# Decoupling_Board.net
KiCad netlist of a schematic drawn in EAGLE
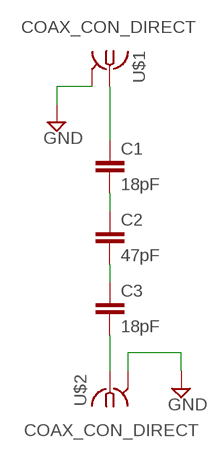
[diagram p0: schematic, sheet 1]

(export (version "E")
  (design (tool "Eeschema 10.0.6"))
  (components
    (comp (ref "C1")
      (value "18pF")
      (footprint "eagle-import:C1210")
      (libsource (lib "eagle-import") (part "C-EUC1210"))
    )
    (comp (ref "C2")
      (value "47pF")
      (footprint "eagle-import:C1210")
      (libsource (lib "eagle-import") (part "C-EUC1210"))
    )
    (comp (ref "C3")
      (value "18pF")
      (footprint "eagle-import:C1210")
      (libsource (lib "eagle-import") (part "C-EUC1210"))
    )
    (comp (ref "U$1")
      (value "COAX_CON_DIRECT")
      (footprint "eagle-import:COAX.141")
      (libsource (lib "eagle-import") (part "COAX_CON_DIRECT"))
    )
    (comp (ref "U$2")
      (value "COAX_CON_DIRECT")
      (footprint "eagle-import:COAX.141")
      (libsource (lib "eagle-import") (part "COAX_CON_DIRECT"))
    )
  )
  (nets
    (net (code "1") (name "GND") (class "Default")
      (node (ref "U$1") (pin "P$2") (pinfunction "GND_P$2") (pintype "passive"))
      (node (ref "U$2") (pin "P$2") (pinfunction "GND_P$2") (pintype "passive"))
    )
    (net (code "2") (name "Net-(C1-Pad2)") (class "Default")
      (node (ref "C1") (pin "2") (pinfunction "2_2") (pintype "passive"))
      (node (ref "C2") (pin "1") (pinfunction "1_1") (pintype "passive"))
    )
    (net (code "3") (name "Net-(C2-Pad2)") (class "Default")
      (node (ref "C2") (pin "2") (pinfunction "2_2") (pintype "passive"))
      (node (ref "C3") (pin "1") (pinfunction "1_1") (pintype "passive"))
    )
    (net (code "4") (name "Net-(U$1-1)") (class "Default")
      (node (ref "C1") (pin "1") (pinfunction "1_1") (pintype "passive"))
      (node (ref "U$1") (pin "P$1") (pinfunction "1_P$1") (pintype "passive"))
    )
    (net (code "5") (name "Net-(U$2-1)") (class "Default")
      (node (ref "C3") (pin "2") (pinfunction "2_2") (pintype "passive"))
      (node (ref "U$2") (pin "P$1") (pinfunction "1_P$1") (pintype "passive"))
    )
  )
)
